# current_monitor_v2.net
KiCad netlist of a schematic drawn in EAGLE
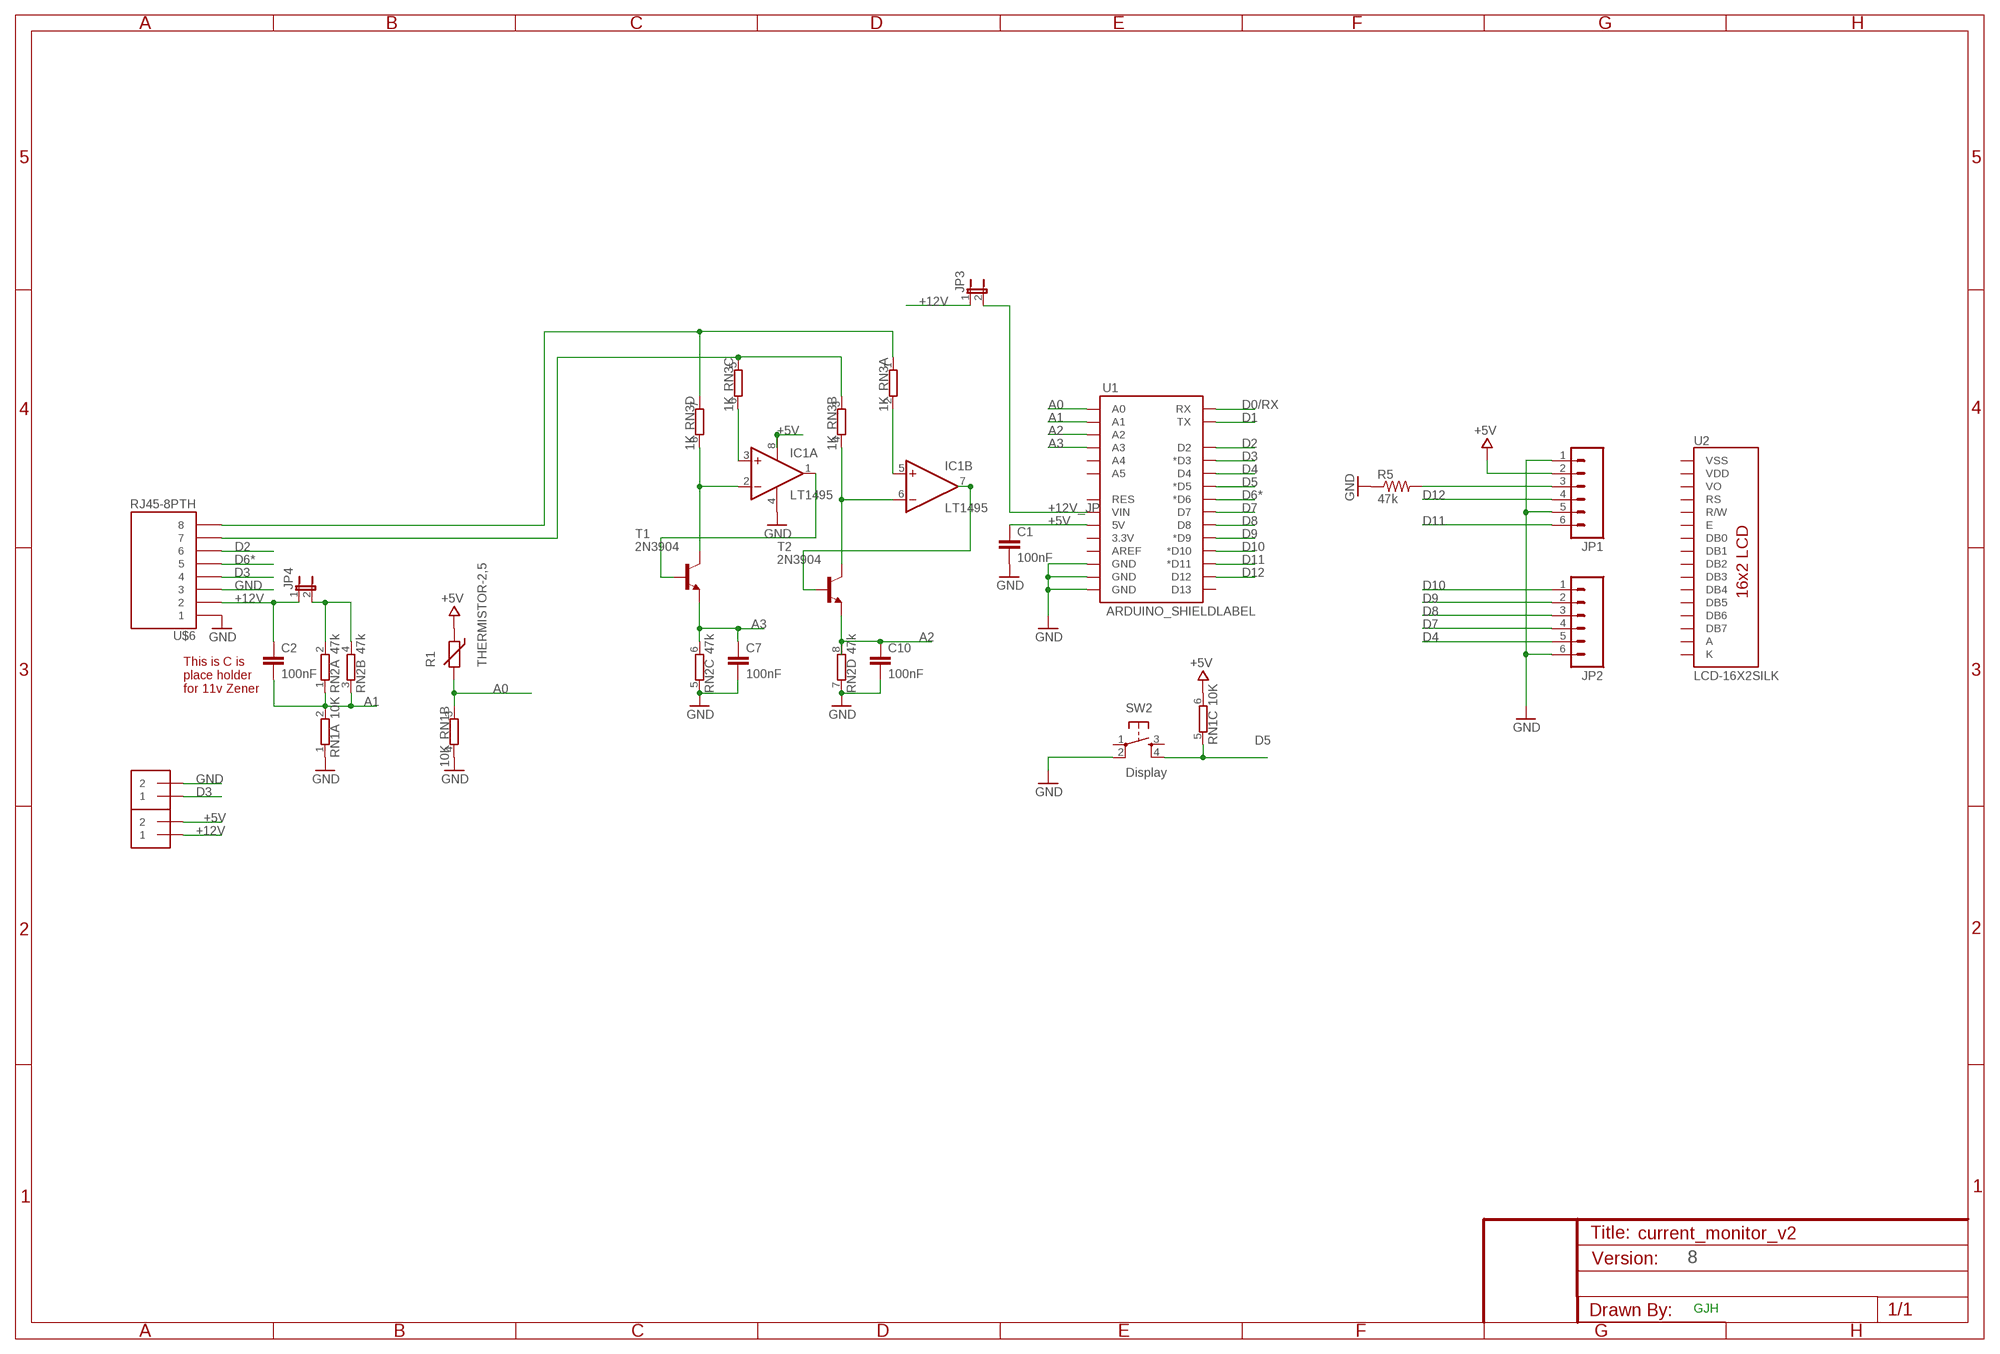
[diagram p0: schematic, sheet 1]

(export (version "E")
  (design (tool "Eeschema 10.0.6"))
  (components
    (comp (ref "C1")
      (value "100nF")
      (footprint "eagle-import:CAP-PTH-5MM")
      (libsource (lib "eagle-import") (part "CAPPTH1"))
    )
    (comp (ref "C2")
      (value "100nF")
      (footprint "eagle-import:CAP-PTH-5MM")
      (libsource (lib "eagle-import") (part "CAPPTH1"))
    )
    (comp (ref "C7")
      (value "100nF")
      (footprint "eagle-import:CAP-PTH-5MM")
      (libsource (lib "eagle-import") (part "CAPPTH1"))
    )
    (comp (ref "C10")
      (value "100nF")
      (footprint "eagle-import:CAP-PTH-5MM")
      (libsource (lib "eagle-import") (part "CAPPTH1"))
    )
    (comp (ref "IC1")
      (value "LT1495")
      (footprint "eagle-import:SOCKED-08")
      (libsource (lib "eagle-import") (part "TL072S"))
    )
    (comp (ref "J1")
      (value "1X2-3.5MM")
      (footprint "eagle-import:1X2-3.5MM")
      (libsource (lib "eagle-import") (part "1X2-3.5MM"))
    )
    (comp (ref "J2")
      (value "1X2-3.5MM")
      (footprint "eagle-import:1X2-3.5MM")
      (libsource (lib "eagle-import") (part "1X2-3.5MM"))
    )
    (comp (ref "JP1")
      (value "M06FEMALE_LOCK")
      (footprint "eagle-import:1X06_FEMALE_LOCK.010")
      (libsource (lib "eagle-import") (part "M06FEMALE_LOCK"))
    )
    (comp (ref "JP2")
      (value "M06FEMALE_LOCK")
      (footprint "eagle-import:1X06_FEMALE_LOCK.010")
      (libsource (lib "eagle-import") (part "M06FEMALE_LOCK"))
    )
    (comp (ref "JP3")
      (value "JUMPER-2PTH")
      (footprint "eagle-import:1X02")
      (libsource (lib "eagle-import") (part "JUMPER-2PTH"))
    )
    (comp (ref "JP4")
      (value "JUMPER-2PTH")
      (footprint "eagle-import:1X02")
      (libsource (lib "eagle-import") (part "JUMPER-2PTH"))
    )
    (comp (ref "R1")
      (value "THERMISTOR-2,5")
      (footprint "eagle-import:RS-2,5")
      (libsource (lib "eagle-import") (part "THERMISTOR-2,5"))
    )
    (comp (ref "R5")
      (value "47k")
      (footprint "eagle-import:AXIAL-0.3")
      (libsource (lib "eagle-import") (part "RESISTORAXIAL-0.3"))
    )
    (comp (ref "RN1")
      (value "10K")
      (footprint "eagle-import:SIL6")
      (libsource (lib "eagle-import") (part "E3R"))
    )
    (comp (ref "RN2")
      (value "47k")
      (footprint "eagle-import:SIL8")
      (libsource (lib "eagle-import") (part "E4R"))
    )
    (comp (ref "RN3")
      (value "1K")
      (footprint "eagle-import:SIL8")
      (libsource (lib "eagle-import") (part "E4R"))
    )
    (comp (ref "SW2")
      (value "Display")
      (footprint "eagle-import:TACTILE-PTH")
      (libsource (lib "eagle-import") (part "TAC_SWITCHPTH"))
    )
    (comp (ref "T1")
      (value "2N3904")
      (footprint "eagle-import:TO92-EBC-OVAL")
      (libsource (lib "eagle-import") (part "2N2222"))
    )
    (comp (ref "T2")
      (value "2N3904")
      (footprint "eagle-import:TO92-EBC-OVAL")
      (libsource (lib "eagle-import") (part "2N2222"))
    )
    (comp (ref "U$6")
      (value "RJ45-8PTH")
      (footprint "eagle-import:RJ45-8")
      (libsource (lib "eagle-import") (part "RJ45-8PTH"))
    )
    (comp (ref "U1")
      (value "ARDUINO_SHIELDLABEL")
      (footprint "eagle-import:DUEMILANOVE_SHIELD")
      (libsource (lib "eagle-import") (part "ARDUINO_SHIELDLABEL"))
    )
    (comp (ref "U2")
      (value "LCD-16X2SILK")
      (footprint "eagle-import:LCD-16X2")
      (libsource (lib "eagle-import") (part "LCD-16X2SILK"))
    )
  )
  (nets
    (net (code "1") (name "+5V") (class "Default")
      (node (ref "C1") (pin "1") (pinfunction "1_1") (pintype "passive"))
      (node (ref "IC1") (pin "8") (pinfunction "V+_8") (pintype "power_in"))
      (node (ref "J2") (pin "2") (pinfunction "2_2") (pintype "passive"))
      (node (ref "JP1") (pin "2") (pinfunction "2_2") (pintype "passive"))
      (node (ref "R1") (pin "1") (pinfunction "1_1") (pintype "passive"))
      (node (ref "RN1") (pin "6") (pinfunction "2_6") (pintype "passive"))
      (node (ref "U1") (pin "5V") (pinfunction "5V_5V") (pintype "bidirectional"))
    )
    (net (code "2") (name "/+12V") (class "Default")
      (node (ref "C2") (pin "1") (pinfunction "1_1") (pintype "passive"))
      (node (ref "J2") (pin "1") (pinfunction "1_1") (pintype "passive"))
      (node (ref "JP3") (pin "1") (pinfunction "1_1") (pintype "passive"))
      (node (ref "JP4") (pin "1") (pinfunction "1_1") (pintype "passive"))
      (node (ref "U$6") (pin "2") (pinfunction "2_2") (pintype "bidirectional"))
    )
    (net (code "3") (name "/+12V_JP") (class "Default")
      (node (ref "JP3") (pin "2") (pinfunction "2_2") (pintype "passive"))
      (node (ref "U1") (pin "VIN") (pinfunction "VIN_VIN") (pintype "bidirectional"))
    )
    (net (code "4") (name "/A") (class "Default")
      (node (ref "U2") (pin "15") (pinfunction "A_15") (pintype "power_in"))
    )
    (net (code "5") (name "/A0") (class "Default")
      (node (ref "R1") (pin "2") (pinfunction "2_2") (pintype "passive"))
      (node (ref "RN1") (pin "3") (pinfunction "1_3") (pintype "passive"))
      (node (ref "U1") (pin "A0") (pinfunction "A0_A0") (pintype "bidirectional"))
    )
    (net (code "6") (name "/A1") (class "Default")
      (node (ref "C2") (pin "2") (pinfunction "2_2") (pintype "passive"))
      (node (ref "RN1") (pin "2") (pinfunction "2_2") (pintype "passive"))
      (node (ref "RN2") (pin "1") (pinfunction "1_1") (pintype "passive"))
      (node (ref "RN2") (pin "3") (pinfunction "1_3") (pintype "passive"))
      (node (ref "U1") (pin "A1") (pinfunction "A1_A1") (pintype "bidirectional"))
    )
    (net (code "7") (name "/A2") (class "Default")
      (node (ref "C10") (pin "1") (pinfunction "1_1") (pintype "passive"))
      (node (ref "RN2") (pin "8") (pinfunction "2_8") (pintype "passive"))
      (node (ref "T2") (pin "E") (pinfunction "E_E") (pintype "passive"))
      (node (ref "U1") (pin "A2") (pinfunction "A2_A2") (pintype "bidirectional"))
    )
    (net (code "8") (name "/A3") (class "Default")
      (node (ref "C7") (pin "1") (pinfunction "1_1") (pintype "passive"))
      (node (ref "RN2") (pin "6") (pinfunction "2_6") (pintype "passive"))
      (node (ref "T1") (pin "E") (pinfunction "E_E") (pintype "passive"))
      (node (ref "U1") (pin "A3") (pinfunction "A3_A3") (pintype "bidirectional"))
    )
    (net (code "9") (name "/D0{slash}RX") (class "Default")
      (node (ref "U1") (pin "RX") (pinfunction "RX_RX") (pintype "bidirectional"))
    )
    (net (code "10") (name "/D1") (class "Default")
      (node (ref "U1") (pin "TX") (pinfunction "TX_TX") (pintype "bidirectional"))
    )
    (net (code "11") (name "/D2") (class "Default")
      (node (ref "U$6") (pin "6") (pinfunction "6_6") (pintype "bidirectional"))
      (node (ref "U1") (pin "D2") (pinfunction "D2_D2") (pintype "bidirectional"))
    )
    (net (code "12") (name "/D3") (class "Default")
      (node (ref "J1") (pin "1") (pinfunction "1_1") (pintype "passive"))
      (node (ref "U$6") (pin "4") (pinfunction "4_4") (pintype "bidirectional"))
      (node (ref "U1") (pin "D3") (pinfunction "*D3_D3") (pintype "bidirectional"))
    )
    (net (code "13") (name "/D4") (class "Default")
      (node (ref "JP2") (pin "5") (pinfunction "5_5") (pintype "passive"))
      (node (ref "U1") (pin "D4") (pinfunction "D4_D4") (pintype "bidirectional"))
    )
    (net (code "14") (name "/D5") (class "Default")
      (node (ref "RN1") (pin "5") (pinfunction "1_5") (pintype "passive"))
      (node (ref "SW2") (pin "4") (pinfunction "4_4") (pintype "passive"))
      (node (ref "U1") (pin "D5") (pinfunction "*D5_D5") (pintype "bidirectional"))
    )
    (net (code "15") (name "/D6*") (class "Default")
      (node (ref "U$6") (pin "5") (pinfunction "5_5") (pintype "bidirectional"))
      (node (ref "U1") (pin "D6") (pinfunction "*D6_D6") (pintype "bidirectional"))
    )
    (net (code "16") (name "/D7") (class "Default")
      (node (ref "JP2") (pin "4") (pinfunction "4_4") (pintype "passive"))
      (node (ref "U1") (pin "D7") (pinfunction "D7_D7") (pintype "bidirectional"))
    )
    (net (code "17") (name "/D8") (class "Default")
      (node (ref "JP2") (pin "3") (pinfunction "3_3") (pintype "passive"))
      (node (ref "U1") (pin "D8") (pinfunction "D8_D8") (pintype "bidirectional"))
    )
    (net (code "18") (name "/D9") (class "Default")
      (node (ref "JP2") (pin "2") (pinfunction "2_2") (pintype "passive"))
      (node (ref "U1") (pin "D9") (pinfunction "*D9_D9") (pintype "bidirectional"))
    )
    (net (code "19") (name "/D10") (class "Default")
      (node (ref "JP2") (pin "1") (pinfunction "1_1") (pintype "passive"))
      (node (ref "U1") (pin "D10") (pinfunction "*D10_D10") (pintype "bidirectional"))
    )
    (net (code "20") (name "/D11") (class "Default")
      (node (ref "JP1") (pin "6") (pinfunction "6_6") (pintype "passive"))
      (node (ref "U1") (pin "D11") (pinfunction "*D11_D11") (pintype "bidirectional"))
    )
    (net (code "21") (name "/D12") (class "Default")
      (node (ref "JP1") (pin "4") (pinfunction "4_4") (pintype "passive"))
      (node (ref "U1") (pin "D12") (pinfunction "D12_D12") (pintype "bidirectional"))
    )
    (net (code "22") (name "/K") (class "Default")
      (node (ref "U2") (pin "16") (pinfunction "K_16") (pintype "power_in"))
    )
    (net (code "23") (name "/VDD") (class "Default")
      (node (ref "U2") (pin "2") (pinfunction "VDD_2") (pintype "power_in"))
    )
    (net (code "24") (name "/VSS") (class "Default")
      (node (ref "U2") (pin "1") (pinfunction "VSS_1") (pintype "power_in"))
    )
    (net (code "25") (name "GND") (class "Default")
      (node (ref "C1") (pin "2") (pinfunction "2_2") (pintype "passive"))
      (node (ref "C10") (pin "2") (pinfunction "2_2") (pintype "passive"))
      (node (ref "C7") (pin "2") (pinfunction "2_2") (pintype "passive"))
      (node (ref "IC1") (pin "4") (pinfunction "V-_4") (pintype "power_in"))
      (node (ref "J1") (pin "2") (pinfunction "2_2") (pintype "passive"))
      (node (ref "JP1") (pin "1") (pinfunction "1_1") (pintype "passive"))
      (node (ref "JP1") (pin "5") (pinfunction "5_5") (pintype "passive"))
      (node (ref "JP2") (pin "6") (pinfunction "6_6") (pintype "passive"))
      (node (ref "R5") (pin "P$1") (pinfunction "1_P$1") (pintype "passive"))
      (node (ref "RN1") (pin "1") (pinfunction "1_1") (pintype "passive"))
      (node (ref "RN1") (pin "4") (pinfunction "2_4") (pintype "passive"))
      (node (ref "RN2") (pin "5") (pinfunction "1_5") (pintype "passive"))
      (node (ref "RN2") (pin "7") (pinfunction "1_7") (pintype "passive"))
      (node (ref "SW2") (pin "2") (pinfunction "2_2") (pintype "passive"))
      (node (ref "U$6") (pin "1") (pinfunction "1_1") (pintype "bidirectional"))
      (node (ref "U$6") (pin "3") (pinfunction "3_3") (pintype "bidirectional"))
      (node (ref "U1") (pin "GND@0") (pinfunction "GND_GND@0") (pintype "bidirectional"))
      (node (ref "U1") (pin "GND@1") (pinfunction "GND_GND@1") (pintype "bidirectional"))
      (node (ref "U1") (pin "GND@2") (pinfunction "GND_GND@2") (pintype "bidirectional"))
    )
    (net (code "26") (name "Net-(IC1A-+IN)") (class "Default")
      (node (ref "IC1") (pin "3") (pinfunction "+IN_3") (pintype "input"))
      (node (ref "RN3") (pin "6") (pinfunction "2_6") (pintype "passive"))
    )
    (net (code "27") (name "Net-(IC1A--IN)") (class "Default")
      (node (ref "IC1") (pin "2") (pinfunction "-IN_2") (pintype "input"))
      (node (ref "RN3") (pin "8") (pinfunction "2_8") (pintype "passive"))
      (node (ref "T1") (pin "C") (pinfunction "C_C") (pintype "passive"))
    )
    (net (code "28") (name "Net-(IC1A-OUT)") (class "Default")
      (node (ref "IC1") (pin "1") (pinfunction "OUT_1") (pintype "output"))
      (node (ref "T1") (pin "B") (pinfunction "B_B") (pintype "passive"))
    )
    (net (code "29") (name "Net-(IC1B-+IN)") (class "Default")
      (node (ref "IC1") (pin "5") (pinfunction "+IN_5") (pintype "input"))
      (node (ref "RN3") (pin "2") (pinfunction "2_2") (pintype "passive"))
    )
    (net (code "30") (name "Net-(IC1B--IN)") (class "Default")
      (node (ref "IC1") (pin "6") (pinfunction "-IN_6") (pintype "input"))
      (node (ref "RN3") (pin "4") (pinfunction "2_4") (pintype "passive"))
      (node (ref "T2") (pin "C") (pinfunction "C_C") (pintype "passive"))
    )
    (net (code "31") (name "Net-(IC1B-OUT)") (class "Default")
      (node (ref "IC1") (pin "7") (pinfunction "OUT_7") (pintype "output"))
      (node (ref "T2") (pin "B") (pinfunction "B_B") (pintype "passive"))
    )
    (net (code "32") (name "Net-(R5-2)") (class "Default")
      (node (ref "JP1") (pin "3") (pinfunction "3_3") (pintype "passive"))
      (node (ref "R5") (pin "P$2") (pinfunction "2_P$2") (pintype "passive"))
    )
    (net (code "33") (name "Net-(RN2B-2)") (class "Default")
      (node (ref "JP4") (pin "2") (pinfunction "2_2") (pintype "passive"))
      (node (ref "RN2") (pin "2") (pinfunction "2_2") (pintype "passive"))
      (node (ref "RN2") (pin "4") (pinfunction "2_4") (pintype "passive"))
    )
    (net (code "34") (name "Net-(RN3B-1)") (class "Default")
      (node (ref "RN3") (pin "3") (pinfunction "1_3") (pintype "passive"))
      (node (ref "RN3") (pin "5") (pinfunction "1_5") (pintype "passive"))
      (node (ref "U$6") (pin "7") (pinfunction "7_7") (pintype "bidirectional"))
    )
    (net (code "35") (name "Net-(RN3D-1)") (class "Default")
      (node (ref "RN3") (pin "1") (pinfunction "1_1") (pintype "passive"))
      (node (ref "RN3") (pin "7") (pinfunction "1_7") (pintype "passive"))
      (node (ref "U$6") (pin "8") (pinfunction "8_8") (pintype "bidirectional"))
    )
    (net (code "36") (name "unconnected-(SW2-Pad1)") (class "Default")
      (node (ref "SW2") (pin "1") (pinfunction "1_1") (pintype "passive"))
    )
    (net (code "37") (name "unconnected-(SW2-Pad3)") (class "Default")
      (node (ref "SW2") (pin "3") (pinfunction "3_3") (pintype "passive"))
    )
    (net (code "38") (name "unconnected-(U1-Pad3.3V)") (class "Default")
      (node (ref "U1") (pin "3.3V") (pinfunction "3.3V_3.3V") (pintype "bidirectional"))
    )
    (net (code "39") (name "unconnected-(U1-PadA4)") (class "Default")
      (node (ref "U1") (pin "A4") (pinfunction "A4_A4") (pintype "bidirectional"))
    )
    (net (code "40") (name "unconnected-(U1-PadA5)") (class "Default")
      (node (ref "U1") (pin "A5") (pinfunction "A5_A5") (pintype "bidirectional"))
    )
    (net (code "41") (name "unconnected-(U1-PadAREF)") (class "Default")
      (node (ref "U1") (pin "AREF") (pinfunction "AREF_AREF") (pintype "bidirectional"))
    )
    (net (code "42") (name "unconnected-(U1-PadD13)") (class "Default")
      (node (ref "U1") (pin "D13") (pinfunction "D13_D13") (pintype "bidirectional"))
    )
    (net (code "43") (name "unconnected-(U1-PadRES)") (class "Default")
      (node (ref "U1") (pin "RES") (pinfunction "RES_RES") (pintype "bidirectional"))
    )
    (net (code "44") (name "unconnected-(U2-DB0-Pad7)") (class "Default")
      (node (ref "U2") (pin "7") (pinfunction "DB0_7") (pintype "bidirectional"))
    )
    (net (code "45") (name "unconnected-(U2-DB1-Pad8)") (class "Default")
      (node (ref "U2") (pin "8") (pinfunction "DB1_8") (pintype "bidirectional"))
    )
    (net (code "46") (name "unconnected-(U2-DB2-Pad9)") (class "Default")
      (node (ref "U2") (pin "9") (pinfunction "DB2_9") (pintype "bidirectional"))
    )
    (net (code "47") (name "unconnected-(U2-DB3-Pad10)") (class "Default")
      (node (ref "U2") (pin "10") (pinfunction "DB3_10") (pintype "bidirectional"))
    )
    (net (code "48") (name "unconnected-(U2-DB4-Pad11)") (class "Default")
      (node (ref "U2") (pin "11") (pinfunction "DB4_11") (pintype "bidirectional"))
    )
    (net (code "49") (name "unconnected-(U2-DB5-Pad12)") (class "Default")
      (node (ref "U2") (pin "12") (pinfunction "DB5_12") (pintype "bidirectional"))
    )
    (net (code "50") (name "unconnected-(U2-DB6-Pad13)") (class "Default")
      (node (ref "U2") (pin "13") (pinfunction "DB6_13") (pintype "bidirectional"))
    )
    (net (code "51") (name "unconnected-(U2-DB7-Pad14)") (class "Default")
      (node (ref "U2") (pin "14") (pinfunction "DB7_14") (pintype "bidirectional"))
    )
    (net (code "52") (name "unconnected-(U2-E-Pad6)") (class "Default")
      (node (ref "U2") (pin "6") (pinfunction "E_6") (pintype "input"))
    )
    (net (code "53") (name "unconnected-(U2-RS-Pad4)") (class "Default")
      (node (ref "U2") (pin "4") (pinfunction "RS_4") (pintype "input"))
    )
    (net (code "54") (name "unconnected-(U2-R{slash}W-Pad5)") (class "Default")
      (node (ref "U2") (pin "5") (pinfunction "R/W_5") (pintype "input"))
    )
    (net (code "55") (name "unconnected-(U2-VO-Pad3)") (class "Default")
      (node (ref "U2") (pin "3") (pinfunction "VO_3") (pintype "bidirectional"))
    )
  )
)
